# receiver.net
KiCad netlist of a schematic drawn in EAGLE
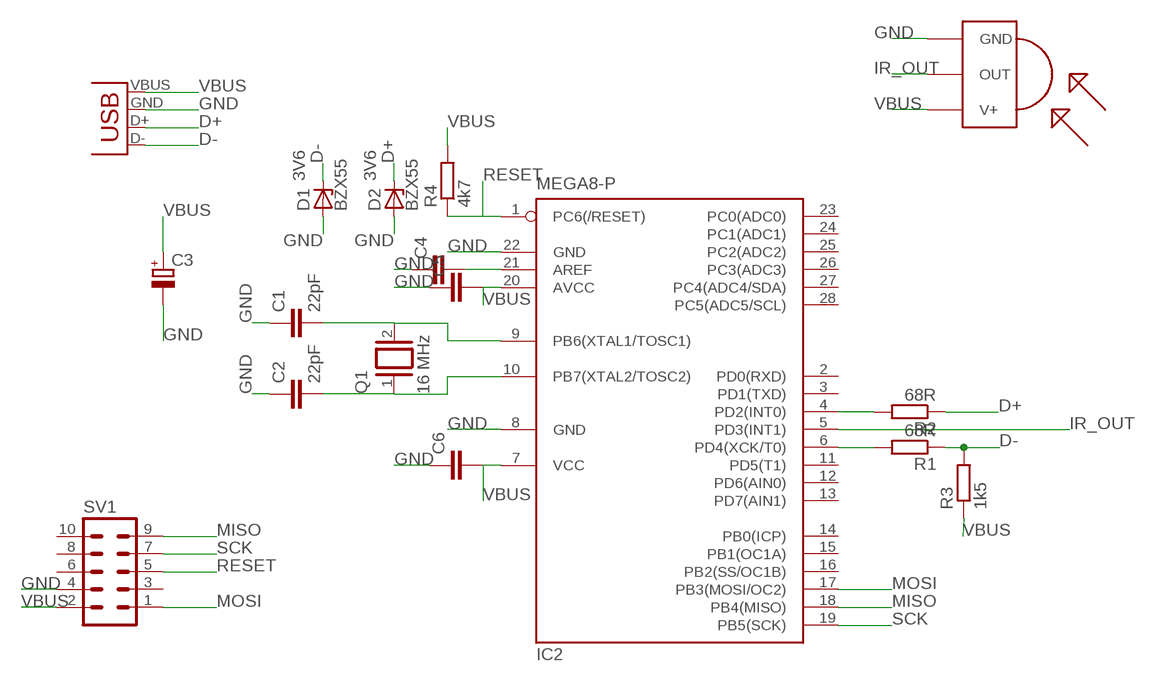
[diagram p0: schematic, sheet 1]

(export (version "E")
  (design (tool "Eeschema 10.0.6"))
  (components
    (comp (ref "C1")
      (value "22pF")
      (footprint "eagle-import:C050-025X075")
      (libsource (lib "eagle-import") (part "resistor_C-EU050-025X075"))
    )
    (comp (ref "C2")
      (value "22pF")
      (footprint "eagle-import:C050-025X075")
      (libsource (lib "eagle-import") (part "resistor_C-EU050-025X075"))
    )
    (comp (ref "C3")
      (value "CPOL-EUE2-5")
      (footprint "eagle-import:E2-5")
      (libsource (lib "eagle-import") (part "CPOL-EUE2-5"))
    )
    (comp (ref "C4")
      (value "C-EU050-024X044")
      (footprint "eagle-import:C050-024X044")
      (libsource (lib "eagle-import") (part "C-EU050-024X044"))
    )
    (comp (ref "C5")
      (value "C-EU050-024X044")
      (footprint "eagle-import:C050-024X044")
      (libsource (lib "eagle-import") (part "C-EU050-024X044"))
    )
    (comp (ref "C6")
      (value "C-EU050-024X044")
      (footprint "eagle-import:C050-024X044")
      (libsource (lib "eagle-import") (part "C-EU050-024X044"))
    )
    (comp (ref "D1")
      (value "BZX55")
      (footprint "eagle-import:DO35Z10")
      (libsource (lib "eagle-import") (part "BZX55"))
    )
    (comp (ref "D2")
      (value "BZX55")
      (footprint "eagle-import:DO35Z10")
      (libsource (lib "eagle-import") (part "BZX55"))
    )
    (comp (ref "IC2")
      (value "MEGA8-P")
      (footprint "eagle-import:DIL28-3")
      (libsource (lib "eagle-import") (part "MEGA8-P"))
    )
    (comp (ref "JP1")
      (value "USB-A-H")
      (footprint "eagle-import:USB-A-H")
      (libsource (lib "eagle-import") (part "USB-A-H"))
    )
    (comp (ref "Q1")
      (value "16 MHz")
      (footprint "eagle-import:QS")
      (libsource (lib "eagle-import") (part "XTAL/S"))
    )
    (comp (ref "R1")
      (value "68R")
      (footprint "eagle-import:0204_7")
      (libsource (lib "eagle-import") (part "R-EU_0204/7"))
    )
    (comp (ref "R2")
      (value "68R")
      (footprint "eagle-import:0204_7")
      (libsource (lib "eagle-import") (part "R-EU_0204/7"))
    )
    (comp (ref "R3")
      (value "1k5")
      (footprint "eagle-import:0204_7")
      (libsource (lib "eagle-import") (part "R-EU_0204/7"))
    )
    (comp (ref "R4")
      (value "4k7")
      (footprint "eagle-import:0204_7")
      (libsource (lib "eagle-import") (part "R-EU_0204/7"))
    )
    (comp (ref "SV1")
      (value "ML10L")
      (footprint "eagle-import:ML10L")
      (libsource (lib "eagle-import") (part "ML10L"))
    )
    (comp (ref "TSOP1")
      (value "TSOP1730")
      (footprint "eagle-import:TSOP17XX")
      (libsource (lib "eagle-import") (part "TSOP1730"))
    )
  )
  (nets
    (net (code "1") (name "/D+") (class "Default")
      (node (ref "D2") (pin "C") (pinfunction "C_C") (pintype "passive"))
      (node (ref "JP1") (pin "D+") (pinfunction "D-_D+") (pintype "bidirectional"))
      (node (ref "R2") (pin "1") (pinfunction "1_1") (pintype "passive"))
    )
    (net (code "2") (name "/D-") (class "Default")
      (node (ref "D1") (pin "C") (pinfunction "C_C") (pintype "passive"))
      (node (ref "JP1") (pin "D-") (pinfunction "D+_D-") (pintype "bidirectional"))
      (node (ref "R1") (pin "1") (pinfunction "1_1") (pintype "passive"))
      (node (ref "R3") (pin "2") (pinfunction "2_2") (pintype "passive"))
    )
    (net (code "3") (name "/GND") (class "Default")
      (node (ref "C1") (pin "1") (pinfunction "1_1") (pintype "passive"))
      (node (ref "C2") (pin "1") (pinfunction "1_1") (pintype "passive"))
      (node (ref "C3") (pin "-") (pinfunction "-_-") (pintype "passive"))
      (node (ref "C4") (pin "1") (pinfunction "1_1") (pintype "passive"))
      (node (ref "C5") (pin "1") (pinfunction "1_1") (pintype "passive"))
      (node (ref "C6") (pin "1") (pinfunction "1_1") (pintype "passive"))
      (node (ref "D1") (pin "A") (pinfunction "A_A") (pintype "passive"))
      (node (ref "D2") (pin "A") (pinfunction "A_A") (pintype "passive"))
      (node (ref "IC2") (pin "22") (pinfunction "GND_22") (pintype "power_in"))
      (node (ref "IC2") (pin "8") (pinfunction "GND_8") (pintype "power_in"))
      (node (ref "JP1") (pin "GND") (pinfunction "VBUS_GND") (pintype "bidirectional"))
      (node (ref "SV1") (pin "4") (pinfunction "4_4") (pintype "passive"))
      (node (ref "TSOP1") (pin "GND") (pinfunction "GND_GND") (pintype "bidirectional"))
    )
    (net (code "4") (name "/IR_OUT") (class "Default")
      (node (ref "IC2") (pin "5") (pinfunction "PD3(INT1)_5") (pintype "bidirectional"))
      (node (ref "TSOP1") (pin "OUT") (pinfunction "OUT_OUT") (pintype "bidirectional"))
    )
    (net (code "5") (name "/MISO") (class "Default")
      (node (ref "IC2") (pin "18") (pinfunction "PB4(MISO)_18") (pintype "bidirectional"))
      (node (ref "SV1") (pin "9") (pinfunction "9_9") (pintype "passive"))
    )
    (net (code "6") (name "/MOSI") (class "Default")
      (node (ref "IC2") (pin "17") (pinfunction "PB3(MOSI/OC2)_17") (pintype "bidirectional"))
      (node (ref "SV1") (pin "1") (pinfunction "1_1") (pintype "passive"))
    )
    (net (code "7") (name "/RESET") (class "Default")
      (node (ref "IC2") (pin "1") (pinfunction "PC6(/RESET)_1") (pintype "bidirectional"))
      (node (ref "R4") (pin "1") (pinfunction "1_1") (pintype "passive"))
      (node (ref "SV1") (pin "5") (pinfunction "5_5") (pintype "passive"))
    )
    (net (code "8") (name "/SCK") (class "Default")
      (node (ref "IC2") (pin "19") (pinfunction "PB5(SCK)_19") (pintype "bidirectional"))
      (node (ref "SV1") (pin "7") (pinfunction "7_7") (pintype "passive"))
    )
    (net (code "9") (name "/VBUS") (class "Default")
      (node (ref "C3") (pin "+") (pinfunction "+_+") (pintype "passive"))
      (node (ref "C5") (pin "2") (pinfunction "2_2") (pintype "passive"))
      (node (ref "C6") (pin "2") (pinfunction "2_2") (pintype "passive"))
      (node (ref "IC2") (pin "20") (pinfunction "AVCC_20") (pintype "power_in"))
      (node (ref "IC2") (pin "7") (pinfunction "VCC_7") (pintype "power_in"))
      (node (ref "JP1") (pin "VBUS") (pinfunction "GND_VBUS") (pintype "bidirectional"))
      (node (ref "R3") (pin "1") (pinfunction "1_1") (pintype "passive"))
      (node (ref "R4") (pin "2") (pinfunction "2_2") (pintype "passive"))
      (node (ref "SV1") (pin "2") (pinfunction "2_2") (pintype "passive"))
      (node (ref "TSOP1") (pin "V+") (pinfunction "V+_V+") (pintype "bidirectional"))
    )
    (net (code "10") (name "Net-(IC2-AREF)") (class "Default")
      (node (ref "C4") (pin "2") (pinfunction "2_2") (pintype "passive"))
      (node (ref "IC2") (pin "21") (pinfunction "AREF_21") (pintype "passive"))
    )
    (net (code "11") (name "Net-(IC2-PB6(XTAL1{slash}TOSC1))") (class "Default")
      (node (ref "C1") (pin "2") (pinfunction "2_2") (pintype "passive"))
      (node (ref "IC2") (pin "9") (pinfunction "PB6(XTAL1/TOSC1)_9") (pintype "bidirectional"))
      (node (ref "Q1") (pin "2") (pinfunction "2_2") (pintype "passive"))
    )
    (net (code "12") (name "Net-(IC2-PB7(XTAL2{slash}TOSC2))") (class "Default")
      (node (ref "C2") (pin "2") (pinfunction "2_2") (pintype "passive"))
      (node (ref "IC2") (pin "10") (pinfunction "PB7(XTAL2/TOSC2)_10") (pintype "bidirectional"))
      (node (ref "Q1") (pin "1") (pinfunction "1_1") (pintype "passive"))
    )
    (net (code "13") (name "Net-(IC2-PD2(INT0))") (class "Default")
      (node (ref "IC2") (pin "4") (pinfunction "PD2(INT0)_4") (pintype "bidirectional"))
      (node (ref "R2") (pin "2") (pinfunction "2_2") (pintype "passive"))
    )
    (net (code "14") (name "Net-(IC2-PD4(XCK{slash}T0))") (class "Default")
      (node (ref "IC2") (pin "6") (pinfunction "PD4(XCK/T0)_6") (pintype "bidirectional"))
      (node (ref "R1") (pin "2") (pinfunction "2_2") (pintype "passive"))
    )
    (net (code "15") (name "unconnected-(IC2-PB0(ICP)-Pad14)") (class "Default")
      (node (ref "IC2") (pin "14") (pinfunction "PB0(ICP)_14") (pintype "bidirectional"))
    )
    (net (code "16") (name "unconnected-(IC2-PB1(OC1A)-Pad15)") (class "Default")
      (node (ref "IC2") (pin "15") (pinfunction "PB1(OC1A)_15") (pintype "bidirectional"))
    )
    (net (code "17") (name "unconnected-(IC2-PB2(SS{slash}OC1B)-Pad16)") (class "Default")
      (node (ref "IC2") (pin "16") (pinfunction "PB2(SS/OC1B)_16") (pintype "bidirectional"))
    )
    (net (code "18") (name "unconnected-(IC2-PC0(ADC0)-Pad23)") (class "Default")
      (node (ref "IC2") (pin "23") (pinfunction "PC0(ADC0)_23") (pintype "bidirectional"))
    )
    (net (code "19") (name "unconnected-(IC2-PC1(ADC1)-Pad24)") (class "Default")
      (node (ref "IC2") (pin "24") (pinfunction "PC1(ADC1)_24") (pintype "bidirectional"))
    )
    (net (code "20") (name "unconnected-(IC2-PC2(ADC2)-Pad25)") (class "Default")
      (node (ref "IC2") (pin "25") (pinfunction "PC2(ADC2)_25") (pintype "bidirectional"))
    )
    (net (code "21") (name "unconnected-(IC2-PC3(ADC3)-Pad26)") (class "Default")
      (node (ref "IC2") (pin "26") (pinfunction "PC3(ADC3)_26") (pintype "bidirectional"))
    )
    (net (code "22") (name "unconnected-(IC2-PC4(ADC4{slash}SDA)-Pad27)") (class "Default")
      (node (ref "IC2") (pin "27") (pinfunction "PC4(ADC4/SDA)_27") (pintype "bidirectional"))
    )
    (net (code "23") (name "unconnected-(IC2-PC5(ADC5{slash}SCL)-Pad28)") (class "Default")
      (node (ref "IC2") (pin "28") (pinfunction "PC5(ADC5/SCL)_28") (pintype "bidirectional"))
    )
    (net (code "24") (name "unconnected-(IC2-PD0(RXD)-Pad2)") (class "Default")
      (node (ref "IC2") (pin "2") (pinfunction "PD0(RXD)_2") (pintype "bidirectional"))
    )
    (net (code "25") (name "unconnected-(IC2-PD1(TXD)-Pad3)") (class "Default")
      (node (ref "IC2") (pin "3") (pinfunction "PD1(TXD)_3") (pintype "bidirectional"))
    )
    (net (code "26") (name "unconnected-(IC2-PD5(T1)-Pad11)") (class "Default")
      (node (ref "IC2") (pin "11") (pinfunction "PD5(T1)_11") (pintype "bidirectional"))
    )
    (net (code "27") (name "unconnected-(IC2-PD6(AIN0)-Pad12)") (class "Default")
      (node (ref "IC2") (pin "12") (pinfunction "PD6(AIN0)_12") (pintype "bidirectional"))
    )
    (net (code "28") (name "unconnected-(IC2-PD7(AIN1)-Pad13)") (class "Default")
      (node (ref "IC2") (pin "13") (pinfunction "PD7(AIN1)_13") (pintype "bidirectional"))
    )
    (net (code "29") (name "unconnected-(SV1-Pad3)") (class "Default")
      (node (ref "SV1") (pin "3") (pinfunction "3_3") (pintype "passive"))
    )
    (net (code "30") (name "unconnected-(SV1-Pad6)") (class "Default")
      (node (ref "SV1") (pin "6") (pinfunction "6_6") (pintype "passive"))
    )
    (net (code "31") (name "unconnected-(SV1-Pad8)") (class "Default")
      (node (ref "SV1") (pin "8") (pinfunction "8_8") (pintype "passive"))
    )
    (net (code "32") (name "unconnected-(SV1-Pad10)") (class "Default")
      (node (ref "SV1") (pin "10") (pinfunction "10_10") (pintype "passive"))
    )
  )
)
